# NES_PSU_Replacement.net
KiCad netlist of a schematic drawn in EAGLE
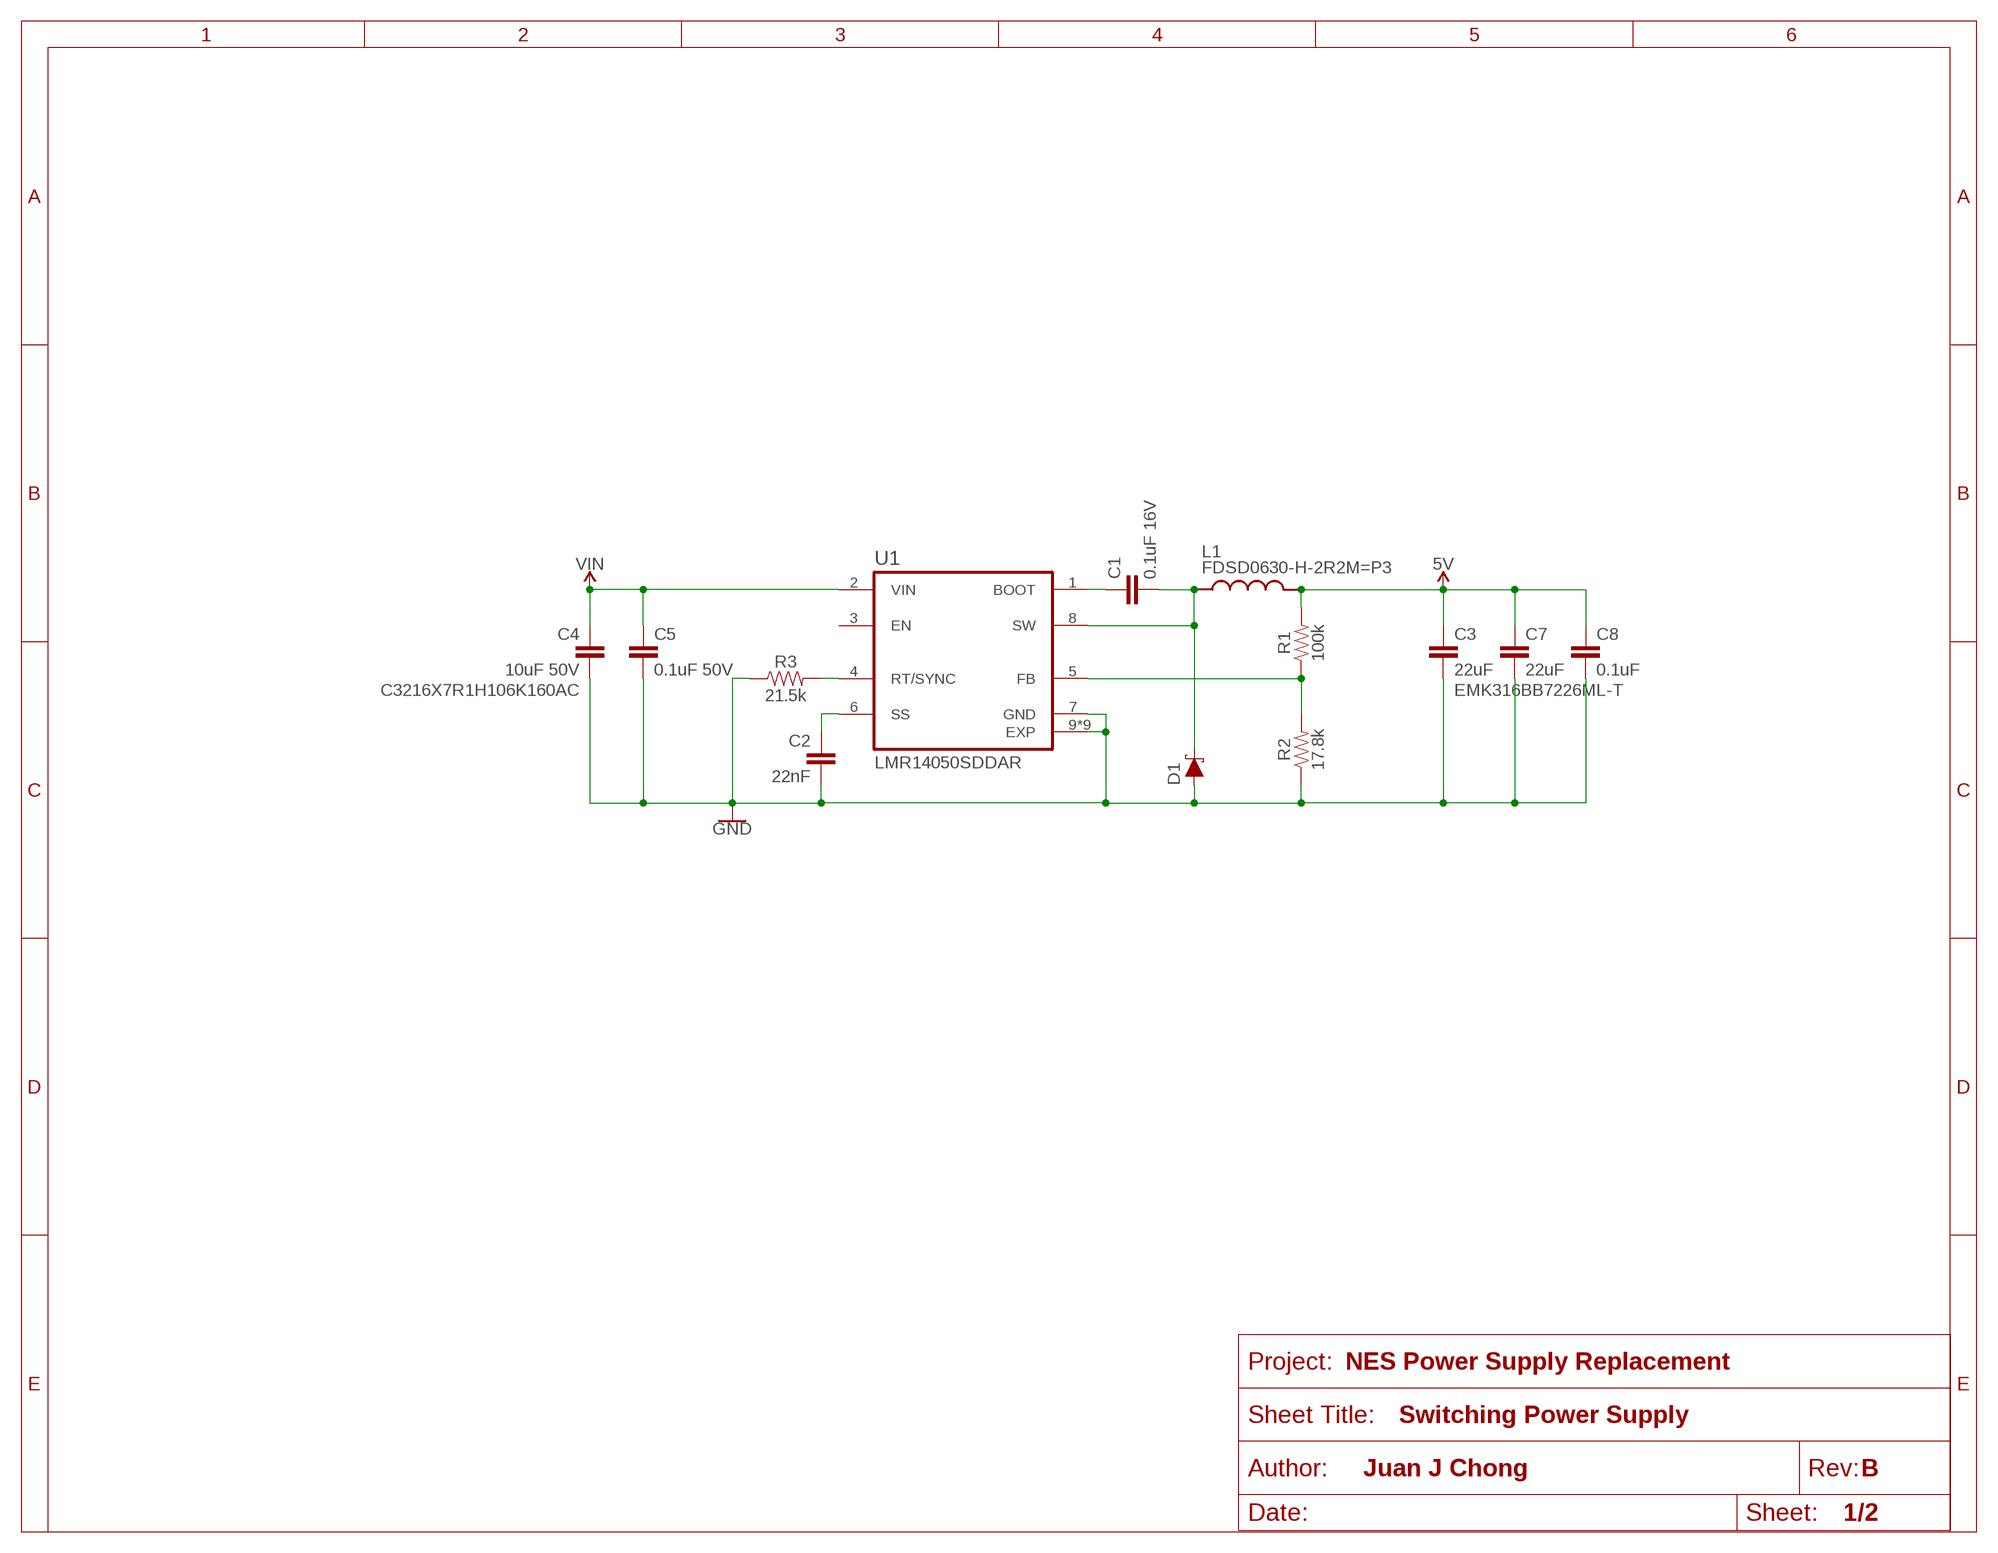
[diagram p0: schematic, sheet 1]
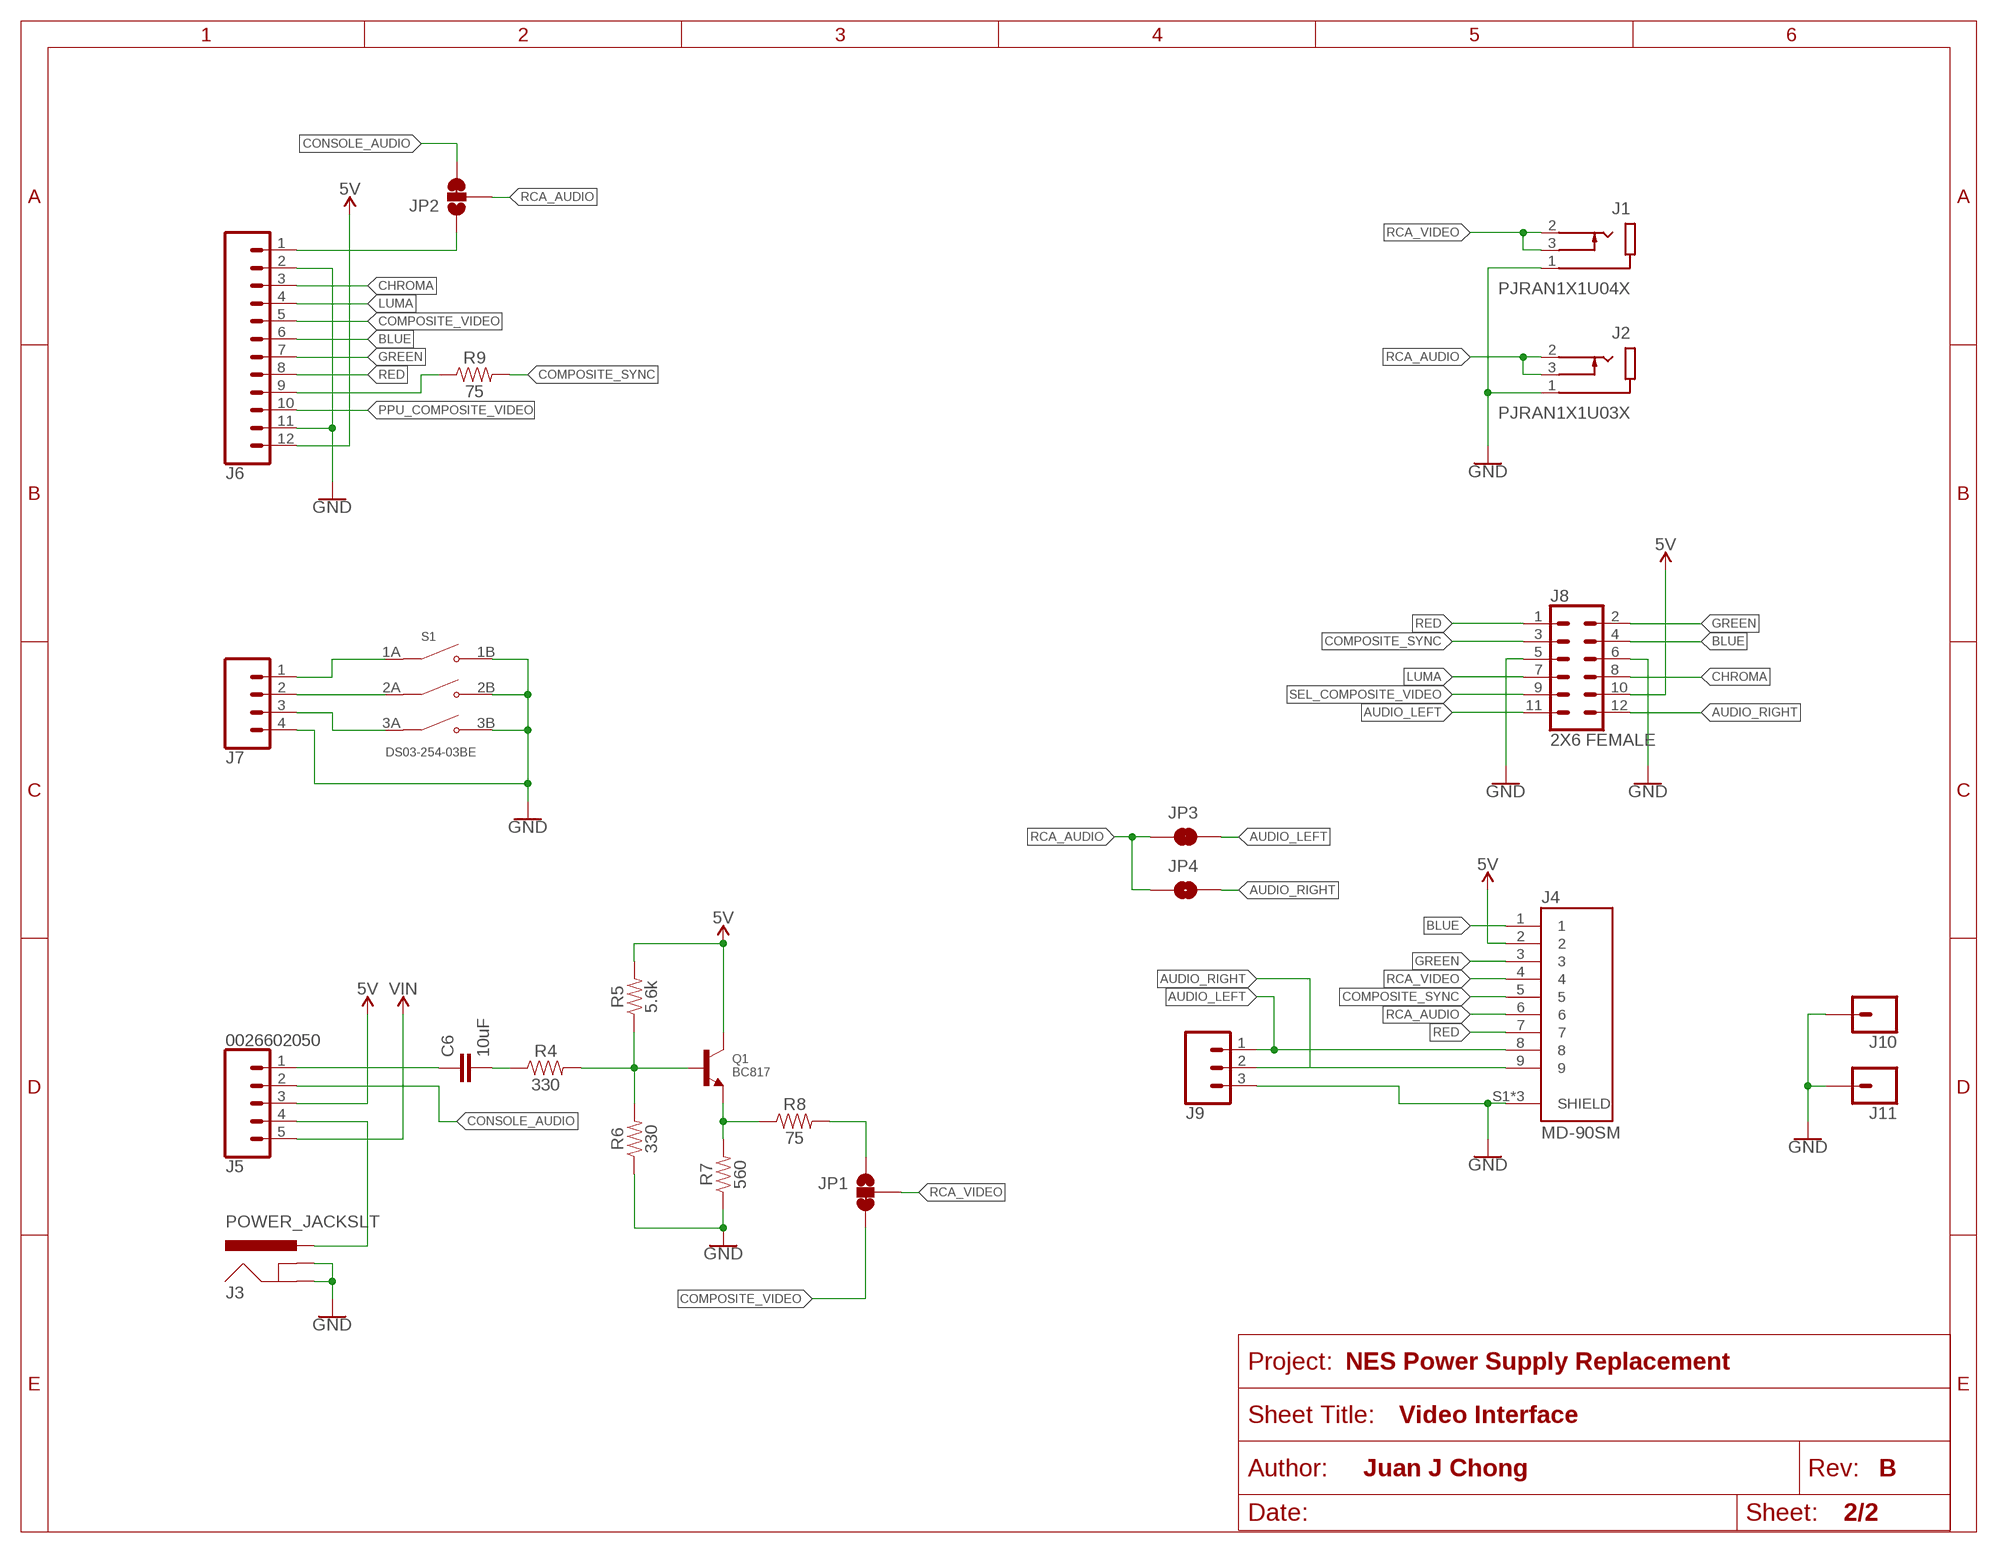
[diagram p1: schematic, sheet 2]

(export (version "E")
  (design (tool "Eeschema 10.0.6"))
  (components
    (comp (ref "C1")
      (value "0.1uF 16V")
      (footprint "eagle-import:0603")
      (libsource (lib "eagle-import") (part "CAP-0603"))
    )
    (comp (ref "C2")
      (value "22nF")
      (footprint "eagle-import:0603")
      (libsource (lib "eagle-import") (part "CAP-0603"))
    )
    (comp (ref "C3")
      (value "22uF")
      (footprint "eagle-import:1206")
      (libsource (lib "eagle-import") (part "CAP-1206"))
    )
    (comp (ref "C4")
      (value "10uF 50V")
      (footprint "eagle-import:1206")
      (libsource (lib "eagle-import") (part "CAP-1206"))
    )
    (comp (ref "C5")
      (value "0.1uF 50V")
      (footprint "eagle-import:0603")
      (libsource (lib "eagle-import") (part "CAP-0603"))
    )
    (comp (ref "C7")
      (value "22uF")
      (footprint "eagle-import:1206")
      (libsource (lib "eagle-import") (part "CAP-1206"))
    )
    (comp (ref "C8")
      (value "0.1uF")
      (footprint "eagle-import:0603")
      (libsource (lib "eagle-import") (part "CAP-0603"))
    )
    (comp (ref "D1")
      (value "1A/15V/220mV")
      (footprint "eagle-import:DO-214AB")
      (libsource (lib "eagle-import") (part "DIODE-SCHOTTKY-SK86C"))
    )
    (comp (ref "L1")
      (value "FDSD0630-H-2R2M=P3")
      (footprint "eagle-import:IND_FDSD0630-H-2R2M=P3")
      (fields (field (name "MF") "Murata"))
      (libsource (lib "eagle-import") (part "FDSD0630-H-2R2M=P3"))
    )
    (comp (ref "R1")
      (value "100k")
      (footprint "eagle-import:0603")
      (libsource (lib "eagle-import") (part "RESISTOR0603"))
    )
    (comp (ref "R2")
      (value "17.8k")
      (footprint "eagle-import:0603")
      (libsource (lib "eagle-import") (part "RESISTOR0603"))
    )
    (comp (ref "R3")
      (value "21.5k")
      (footprint "eagle-import:0603")
      (libsource (lib "eagle-import") (part "RESISTOR0603"))
    )
    (comp (ref "U1")
      (value "LMR14050SDDAR")
      (footprint "eagle-import:VREG_LM5017MR_NOPB")
      (fields (field (name "MF") "Texas Instruments"))
      (libsource (lib "eagle-import") (part "LMR14050SDDAR"))
    )
    (comp (ref "C6")
      (value "10uF")
      (footprint "eagle-import:1206")
      (libsource (lib "eagle-import") (part "CAP-1206"))
    )
    (comp (ref "J1")
      (value "PJRAN1X1U04X")
      (footprint "eagle-import:SWITCHCRAFT_PJRAN1X1U02AUX")
      (fields (field (name "MF") "Switchcraft") (field (name "MP") "PJRAN1X1U02AUX"))
      (libsource (lib "eagle-import") (part "PJRAN1X1U02AUX"))
    )
    (comp (ref "J2")
      (value "PJRAN1X1U03X")
      (footprint "eagle-import:SWITCHCRAFT_PJRAN1X1U02AUX")
      (fields (field (name "MF") "Switchcraft") (field (name "MP") "PJRAN1X1U02AUX"))
      (libsource (lib "eagle-import") (part "PJRAN1X1U02AUX"))
    )
    (comp (ref "J3")
      (value "POWER_JACKSLT")
      (footprint "eagle-import:POWER_JACK_SLOT")
      (libsource (lib "eagle-import") (part "POWER_JACKSLT"))
    )
    (comp (ref "J4")
      (value "MD-90SM")
      (footprint "eagle-import:CUI_MD-90SM")
      (fields (field (name "MF") "CUI Devices"))
      (libsource (lib "eagle-import") (part "MD-90SM"))
    )
    (comp (ref "J5")
      (value "0026602050")
      (footprint "eagle-import:1X05_3.96MM")
      (libsource (lib "eagle-import") (part "CONN_053.96MM"))
    )
    (comp (ref "J6")
      (value "CONN_12LONGPADS")
      (footprint "eagle-import:1X12_LONGPADS")
      (libsource (lib "eagle-import") (part "CONN_12LONGPADS"))
    )
    (comp (ref "J7")
      (value "CONN_04LONGPADS")
      (footprint "eagle-import:1X04_LONGPADS")
      (libsource (lib "eagle-import") (part "CONN_04LONGPADS"))
    )
    (comp (ref "J8")
      (value "2X6 FEMALE")
      (footprint "eagle-import:2X6")
      (libsource (lib "eagle-import") (part "CONN_06X2PTH_FEMALE"))
    )
    (comp (ref "J9")
      (value "CONN_03LONGPADS")
      (footprint "eagle-import:1X03_LONGPADS")
      (libsource (lib "eagle-import") (part "CONN_03LONGPADS"))
    )
    (comp (ref "J10")
      (value "CONN_01KEYSTONE_1216")
      (footprint "eagle-import:1X01_1216")
      (libsource (lib "eagle-import") (part "CONN_01KEYSTONE_1216"))
    )
    (comp (ref "J11")
      (value "CONN_01KEYSTONE_1216")
      (footprint "eagle-import:1X01_1216")
      (libsource (lib "eagle-import") (part "CONN_01KEYSTONE_1216"))
    )
    (comp (ref "JP1")
      (value "JUMPER-SMT_3_1-NC_TRACE_SILK")
      (footprint "eagle-import:SMT-JUMPER_3_1-NC_TRACE_SILK")
      (libsource (lib "eagle-import") (part "JUMPER-SMT_3_1-NC_TRACE_SILK"))
    )
    (comp (ref "JP2")
      (value "JUMPER-SMT_3_1-NC_TRACE_SILK")
      (footprint "eagle-import:SMT-JUMPER_3_1-NC_TRACE_SILK")
      (libsource (lib "eagle-import") (part "JUMPER-SMT_3_1-NC_TRACE_SILK"))
    )
    (comp (ref "JP3")
      (value "JUMPER-SMT_2_NC_TRACE_SILK")
      (footprint "eagle-import:SMT-JUMPER_2_NC_TRACE_SILK")
      (libsource (lib "eagle-import") (part "JUMPER-SMT_2_NC_TRACE_SILK"))
    )
    (comp (ref "JP4")
      (value "JUMPER-SMT_2_NO_SILK")
      (footprint "eagle-import:SMT-JUMPER_2_NO_SILK")
      (libsource (lib "eagle-import") (part "JUMPER-SMT_2_NO_SILK"))
    )
    (comp (ref "Q1")
      (value "BC817")
      (footprint "eagle-import:SOT23-R")
      (libsource (lib "eagle-import") (part "TRANSISTOR_NPN"))
    )
    (comp (ref "R4")
      (value "330")
      (footprint "eagle-import:0603")
      (libsource (lib "eagle-import") (part "RESISTOR0603"))
    )
    (comp (ref "R5")
      (value "5.6k")
      (footprint "eagle-import:0603")
      (libsource (lib "eagle-import") (part "RESISTOR0603"))
    )
    (comp (ref "R6")
      (value "330")
      (footprint "eagle-import:0603")
      (libsource (lib "eagle-import") (part "RESISTOR0603"))
    )
    (comp (ref "R7")
      (value "560")
      (footprint "eagle-import:0603")
      (libsource (lib "eagle-import") (part "RESISTOR0603"))
    )
    (comp (ref "R8")
      (value "75")
      (footprint "eagle-import:0603")
      (libsource (lib "eagle-import") (part "RESISTOR0603"))
    )
    (comp (ref "R9")
      (value "75")
      (footprint "eagle-import:0603")
      (libsource (lib "eagle-import") (part "RESISTOR0603"))
    )
    (comp (ref "S1")
      (value "DS03-254-03BE")
      (footprint "eagle-import:SW_DS03-254-03BE")
      (fields (field (name "MF") "CUI Devices"))
      (libsource (lib "eagle-import") (part "DS03-254-03BE"))
    )
  )
  (nets
    (net (code "1") (name "5V") (class "Default")
      (node (ref "C3") (pin "1") (pinfunction "1_1") (pintype "passive"))
      (node (ref "C7") (pin "1") (pinfunction "1_1") (pintype "passive"))
      (node (ref "C8") (pin "1") (pinfunction "1_1") (pintype "passive"))
      (node (ref "J4") (pin "2") (pinfunction "2_2") (pintype "passive"))
      (node (ref "J5") (pin "3") (pinfunction "3_3") (pintype "passive"))
      (node (ref "J6") (pin "12") (pinfunction "12_12") (pintype "passive"))
      (node (ref "J8") (pin "10") (pinfunction "10_10") (pintype "passive"))
      (node (ref "L1") (pin "2") (pinfunction "2_2") (pintype "passive"))
      (node (ref "Q1") (pin "3") (pinfunction "C_3") (pintype "passive"))
      (node (ref "R1") (pin "2") (pinfunction "2_2") (pintype "passive"))
      (node (ref "R5") (pin "2") (pinfunction "2_2") (pintype "passive"))
    )
    (net (code "2") (name "AUDIO_LEFT") (class "Default")
      (node (ref "J4") (pin "8") (pinfunction "8_8") (pintype "passive"))
      (node (ref "J8") (pin "11") (pinfunction "11_11") (pintype "passive"))
      (node (ref "J9") (pin "1") (pinfunction "1_1") (pintype "passive"))
      (node (ref "JP3") (pin "2") (pinfunction "2_2") (pintype "passive"))
    )
    (net (code "3") (name "AUDIO_RIGHT") (class "Default")
      (node (ref "J4") (pin "9") (pinfunction "9_9") (pintype "passive"))
      (node (ref "J8") (pin "12") (pinfunction "12_12") (pintype "passive"))
      (node (ref "J9") (pin "2") (pinfunction "2_2") (pintype "passive"))
      (node (ref "JP4") (pin "2") (pinfunction "2_2") (pintype "passive"))
    )
    (net (code "4") (name "BLUE") (class "Default")
      (node (ref "J4") (pin "1") (pinfunction "1_1") (pintype "passive"))
      (node (ref "J6") (pin "6") (pinfunction "6_6") (pintype "passive"))
      (node (ref "J8") (pin "4") (pinfunction "4_4") (pintype "passive"))
    )
    (net (code "5") (name "CHROMA") (class "Default")
      (node (ref "J6") (pin "3") (pinfunction "3_3") (pintype "passive"))
      (node (ref "J8") (pin "8") (pinfunction "8_8") (pintype "passive"))
    )
    (net (code "6") (name "COMPOSITE_SYNC") (class "Default")
      (node (ref "J4") (pin "5") (pinfunction "5_5") (pintype "passive"))
      (node (ref "J8") (pin "3") (pinfunction "3_3") (pintype "passive"))
      (node (ref "R9") (pin "2") (pinfunction "2_2") (pintype "passive"))
    )
    (net (code "7") (name "COMPOSITE_VIDEO") (class "Default")
      (node (ref "J6") (pin "5") (pinfunction "5_5") (pintype "passive"))
      (node (ref "JP1") (pin "3") (pinfunction "3_3") (pintype "passive"))
    )
    (net (code "8") (name "CONSOLE_AUDIO") (class "Default")
      (node (ref "J5") (pin "2") (pinfunction "2_2") (pintype "passive"))
      (node (ref "JP2") (pin "3") (pinfunction "3_3") (pintype "passive"))
    )
    (net (code "9") (name "GND") (class "Default")
      (node (ref "C2") (pin "2") (pinfunction "2_2") (pintype "passive"))
      (node (ref "C3") (pin "2") (pinfunction "2_2") (pintype "passive"))
      (node (ref "C4") (pin "2") (pinfunction "2_2") (pintype "passive"))
      (node (ref "C5") (pin "2") (pinfunction "2_2") (pintype "passive"))
      (node (ref "C7") (pin "2") (pinfunction "2_2") (pintype "passive"))
      (node (ref "C8") (pin "2") (pinfunction "2_2") (pintype "passive"))
      (node (ref "D1") (pin "2") (pinfunction "A_2") (pintype "passive"))
      (node (ref "J1") (pin "1") (pinfunction "SLEEVE_1") (pintype "passive"))
      (node (ref "J10") (pin "P$1") (pinfunction "1_P$1") (pintype "passive"))
      (node (ref "J10") (pin "P$2") (pinfunction "1_P$2") (pintype "passive"))
      (node (ref "J11") (pin "P$1") (pinfunction "1_P$1") (pintype "passive"))
      (node (ref "J11") (pin "P$2") (pinfunction "1_P$2") (pintype "passive"))
      (node (ref "J2") (pin "1") (pinfunction "SLEEVE_1") (pintype "passive"))
      (node (ref "J3") (pin "GND@1") (pinfunction "GNDBREAK_GND@1") (pintype "bidirectional"))
      (node (ref "J3") (pin "GND@2") (pinfunction "GND_GND@2") (pintype "bidirectional"))
      (node (ref "J4") (pin "S1") (pinfunction "SHIELD_S1") (pintype "passive"))
      (node (ref "J4") (pin "S2") (pinfunction "SHIELD_S2") (pintype "passive"))
      (node (ref "J4") (pin "S3") (pinfunction "SHIELD_S3") (pintype "passive"))
      (node (ref "J6") (pin "11") (pinfunction "11_11") (pintype "passive"))
      (node (ref "J6") (pin "2") (pinfunction "2_2") (pintype "passive"))
      (node (ref "J7") (pin "4") (pinfunction "4_4") (pintype "passive"))
      (node (ref "J8") (pin "5") (pinfunction "5_5") (pintype "passive"))
      (node (ref "J8") (pin "6") (pinfunction "6_6") (pintype "passive"))
      (node (ref "J9") (pin "3") (pinfunction "3_3") (pintype "passive"))
      (node (ref "R2") (pin "1") (pinfunction "1_1") (pintype "passive"))
      (node (ref "R3") (pin "1") (pinfunction "1_1") (pintype "passive"))
      (node (ref "R6") (pin "1") (pinfunction "1_1") (pintype "passive"))
      (node (ref "R7") (pin "1") (pinfunction "1_1") (pintype "passive"))
      (node (ref "S1") (pin "1B") (pinfunction "NO1_1B") (pintype "passive"))
      (node (ref "S1") (pin "2B") (pinfunction "NO2_2B") (pintype "passive"))
      (node (ref "S1") (pin "3B") (pinfunction "NO3_3B") (pintype "passive"))
      (node (ref "U1") (pin "10") (pinfunction "EXP_10") (pintype "power_in"))
      (node (ref "U1") (pin "11") (pinfunction "EXP_11") (pintype "power_in"))
      (node (ref "U1") (pin "12") (pinfunction "EXP_12") (pintype "power_in"))
      (node (ref "U1") (pin "13") (pinfunction "EXP_13") (pintype "power_in"))
      (node (ref "U1") (pin "14") (pinfunction "EXP_14") (pintype "power_in"))
      (node (ref "U1") (pin "15") (pinfunction "EXP_15") (pintype "power_in"))
      (node (ref "U1") (pin "16") (pinfunction "EXP_16") (pintype "power_in"))
      (node (ref "U1") (pin "17") (pinfunction "EXP_17") (pintype "power_in"))
      (node (ref "U1") (pin "7") (pinfunction "GND_7") (pintype "power_in"))
      (node (ref "U1") (pin "9") (pinfunction "EXP_9") (pintype "power_in"))
    )
    (net (code "10") (name "GREEN") (class "Default")
      (node (ref "J4") (pin "3") (pinfunction "3_3") (pintype "passive"))
      (node (ref "J6") (pin "7") (pinfunction "7_7") (pintype "passive"))
      (node (ref "J8") (pin "2") (pinfunction "2_2") (pintype "passive"))
    )
    (net (code "11") (name "LUMA") (class "Default")
      (node (ref "J6") (pin "4") (pinfunction "4_4") (pintype "passive"))
      (node (ref "J8") (pin "7") (pinfunction "7_7") (pintype "passive"))
    )
    (net (code "12") (name "Net-(C6-Pad1)") (class "Default")
      (node (ref "C6") (pin "1") (pinfunction "1_1") (pintype "passive"))
      (node (ref "J5") (pin "1") (pinfunction "1_1") (pintype "passive"))
    )
    (net (code "13") (name "Net-(C6-Pad2)") (class "Default")
      (node (ref "C6") (pin "2") (pinfunction "2_2") (pintype "passive"))
      (node (ref "R4") (pin "1") (pinfunction "1_1") (pintype "passive"))
    )
    (net (code "14") (name "Net-(D1-C)") (class "Default")
      (node (ref "C1") (pin "2") (pinfunction "2_2") (pintype "passive"))
      (node (ref "D1") (pin "1") (pinfunction "C_1") (pintype "passive"))
      (node (ref "L1") (pin "1") (pinfunction "1_1") (pintype "passive"))
      (node (ref "U1") (pin "8") (pinfunction "SW_8") (pintype "output"))
    )
    (net (code "15") (name "Net-(J3-PadPWR)") (class "Default")
      (node (ref "J3") (pin "PWR") (pinfunction "PWR_PWR") (pintype "bidirectional"))
      (node (ref "J5") (pin "4") (pinfunction "4_4") (pintype "passive"))
    )
    (net (code "16") (name "Net-(J6-Pad1)") (class "Default")
      (node (ref "J6") (pin "1") (pinfunction "1_1") (pintype "passive"))
      (node (ref "JP2") (pin "1") (pinfunction "1_1") (pintype "passive"))
    )
    (net (code "17") (name "Net-(J6-Pad9)") (class "Default")
      (node (ref "J6") (pin "9") (pinfunction "9_9") (pintype "passive"))
      (node (ref "R9") (pin "1") (pinfunction "1_1") (pintype "passive"))
    )
    (net (code "18") (name "Net-(JP1-Pad1)") (class "Default")
      (node (ref "JP1") (pin "1") (pinfunction "1_1") (pintype "passive"))
      (node (ref "R8") (pin "2") (pinfunction "2_2") (pintype "passive"))
    )
    (net (code "19") (name "Net-(Q1-B)") (class "Default")
      (node (ref "Q1") (pin "1") (pinfunction "B_1") (pintype "passive"))
      (node (ref "R4") (pin "2") (pinfunction "2_2") (pintype "passive"))
      (node (ref "R5") (pin "1") (pinfunction "1_1") (pintype "passive"))
      (node (ref "R6") (pin "2") (pinfunction "2_2") (pintype "passive"))
    )
    (net (code "20") (name "Net-(Q1-E)") (class "Default")
      (node (ref "Q1") (pin "2") (pinfunction "E_2") (pintype "passive"))
      (node (ref "R7") (pin "2") (pinfunction "2_2") (pintype "passive"))
      (node (ref "R8") (pin "1") (pinfunction "1_1") (pintype "passive"))
    )
    (net (code "21") (name "Net-(S1-COM1)") (class "Default")
      (node (ref "J7") (pin "1") (pinfunction "1_1") (pintype "passive"))
      (node (ref "S1") (pin "1A") (pinfunction "COM1_1A") (pintype "passive"))
    )
    (net (code "22") (name "Net-(S1-COM2)") (class "Default")
      (node (ref "J7") (pin "2") (pinfunction "2_2") (pintype "passive"))
      (node (ref "S1") (pin "2A") (pinfunction "COM2_2A") (pintype "passive"))
    )
    (net (code "23") (name "Net-(S1-COM3)") (class "Default")
      (node (ref "J7") (pin "3") (pinfunction "3_3") (pintype "passive"))
      (node (ref "S1") (pin "3A") (pinfunction "COM3_3A") (pintype "passive"))
    )
    (net (code "24") (name "Net-(U1-BOOT)") (class "Default")
      (node (ref "C1") (pin "1") (pinfunction "1_1") (pintype "passive"))
      (node (ref "U1") (pin "1") (pinfunction "BOOT_1") (pintype "output"))
    )
    (net (code "25") (name "Net-(U1-FB)") (class "Default")
      (node (ref "R1") (pin "1") (pinfunction "1_1") (pintype "passive"))
      (node (ref "R2") (pin "2") (pinfunction "2_2") (pintype "passive"))
      (node (ref "U1") (pin "5") (pinfunction "FB_5") (pintype "input"))
    )
    (net (code "26") (name "Net-(U1-RT{slash}SYNC)") (class "Default")
      (node (ref "R3") (pin "2") (pinfunction "2_2") (pintype "passive"))
      (node (ref "U1") (pin "4") (pinfunction "RT/SYNC_4") (pintype "input"))
    )
    (net (code "27") (name "Net-(U1-SS)") (class "Default")
      (node (ref "C2") (pin "1") (pinfunction "1_1") (pintype "passive"))
      (node (ref "U1") (pin "6") (pinfunction "SS_6") (pintype "output"))
    )
    (net (code "28") (name "PPU_COMPOSITE_VIDEO") (class "Default")
      (node (ref "J6") (pin "10") (pinfunction "10_10") (pintype "passive"))
    )
    (net (code "29") (name "RCA_AUDIO") (class "Default")
      (node (ref "J2") (pin "2") (pinfunction "TIP_2") (pintype "passive"))
      (node (ref "J2") (pin "3") (pinfunction "SHUNT_3") (pintype "passive"))
      (node (ref "J4") (pin "6") (pinfunction "6_6") (pintype "passive"))
      (node (ref "JP2") (pin "2") (pinfunction "2_2") (pintype "passive"))
      (node (ref "JP3") (pin "1") (pinfunction "1_1") (pintype "passive"))
      (node (ref "JP4") (pin "1") (pinfunction "1_1") (pintype "passive"))
    )
    (net (code "30") (name "RCA_VIDEO") (class "Default")
      (node (ref "J1") (pin "2") (pinfunction "TIP_2") (pintype "passive"))
      (node (ref "J1") (pin "3") (pinfunction "SHUNT_3") (pintype "passive"))
      (node (ref "J4") (pin "4") (pinfunction "4_4") (pintype "passive"))
      (node (ref "JP1") (pin "2") (pinfunction "2_2") (pintype "passive"))
    )
    (net (code "31") (name "RED") (class "Default")
      (node (ref "J4") (pin "7") (pinfunction "7_7") (pintype "passive"))
      (node (ref "J6") (pin "8") (pinfunction "8_8") (pintype "passive"))
      (node (ref "J8") (pin "1") (pinfunction "1_1") (pintype "passive"))
    )
    (net (code "32") (name "SEL_COMPOSITE_VIDEO") (class "Default")
      (node (ref "J8") (pin "9") (pinfunction "9_9") (pintype "passive"))
    )
    (net (code "33") (name "VIN") (class "Default")
      (node (ref "C4") (pin "1") (pinfunction "1_1") (pintype "passive"))
      (node (ref "C5") (pin "1") (pinfunction "1_1") (pintype "passive"))
      (node (ref "J5") (pin "5") (pinfunction "5_5") (pintype "passive"))
      (node (ref "U1") (pin "2") (pinfunction "VIN_2") (pintype "input"))
    )
    (net (code "34") (name "unconnected-(U1-EN-Pad3)") (class "Default")
      (node (ref "U1") (pin "3") (pinfunction "EN_3") (pintype "input"))
    )
  )
)
